# lupa300-card.net
KiCad netlist of a schematic drawn in EAGLE
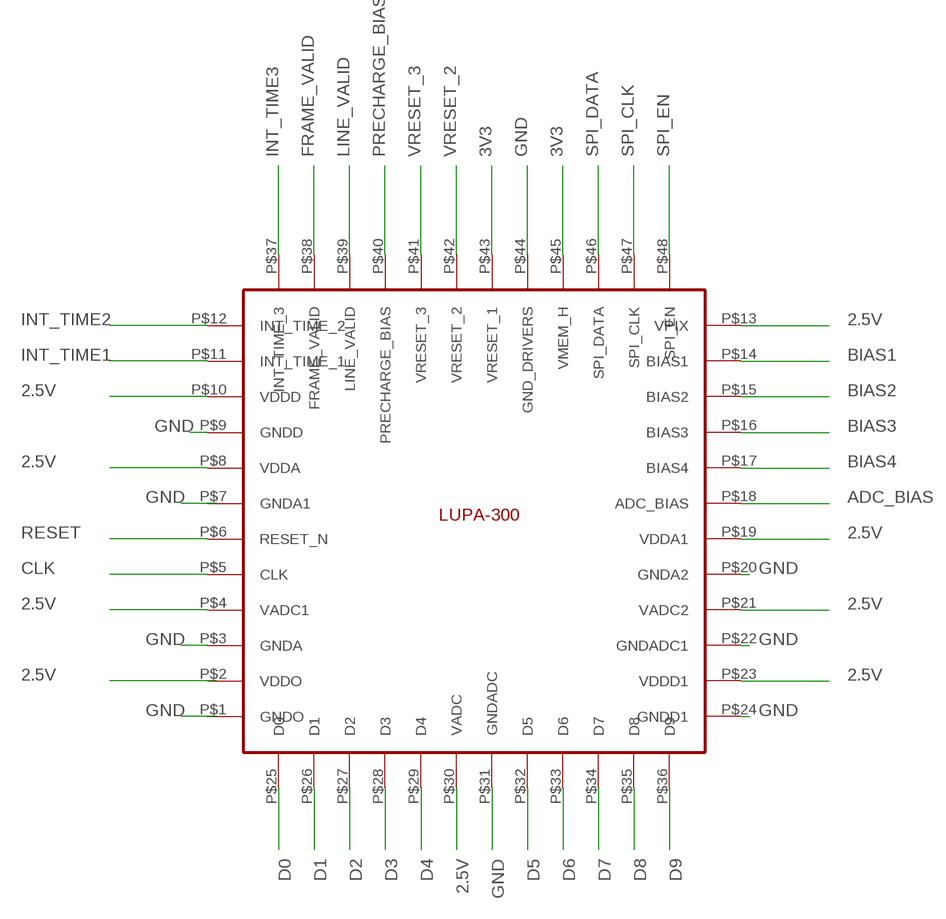
[diagram p0: schematic, sheet 1]
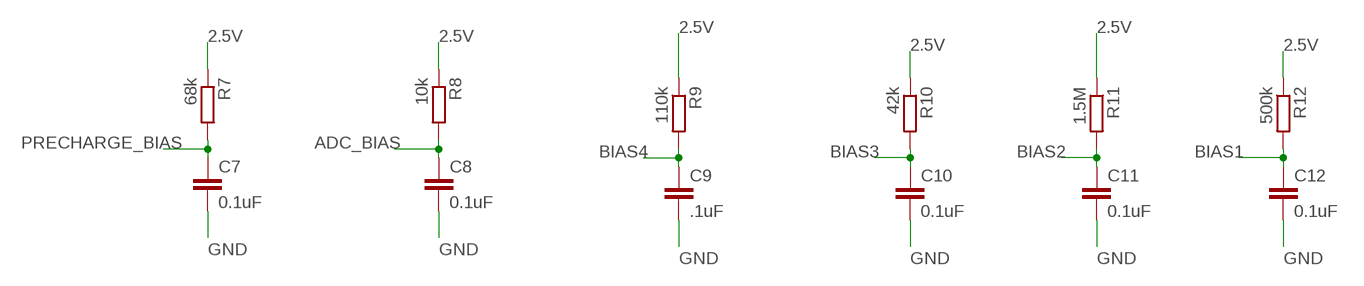
[diagram p1: schematic, sheet 2]
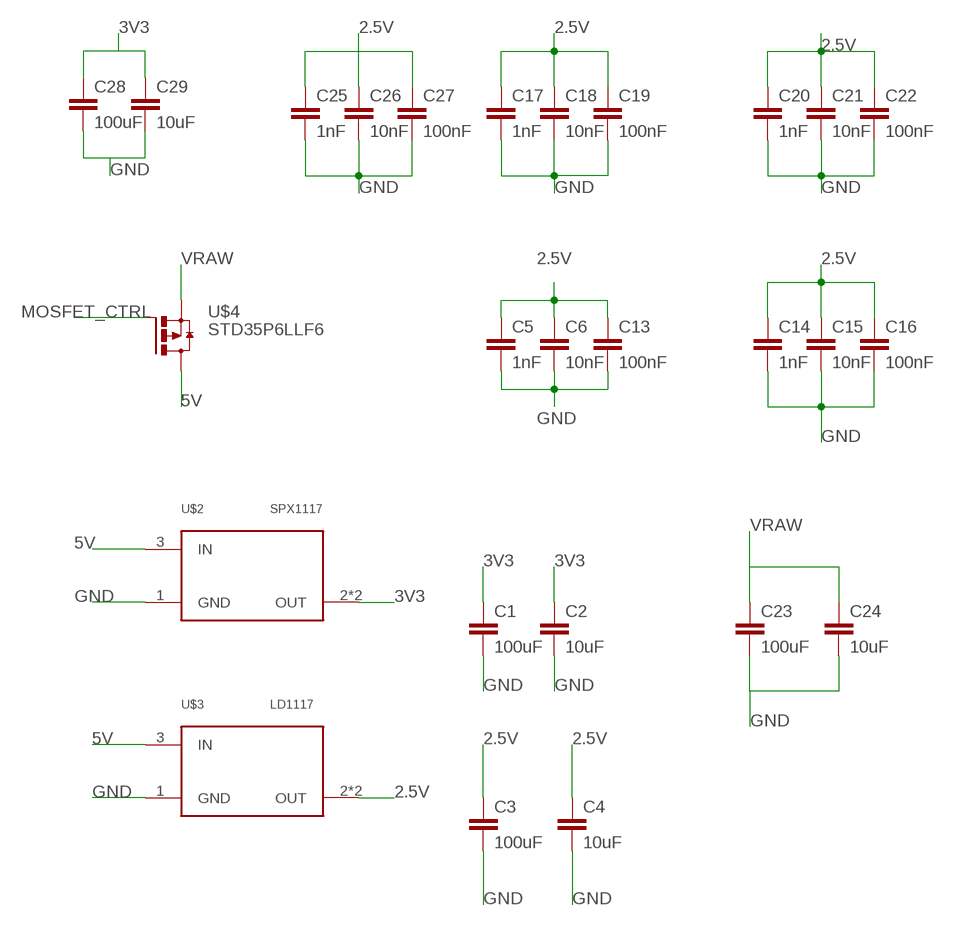
[diagram p2: schematic, sheet 3]
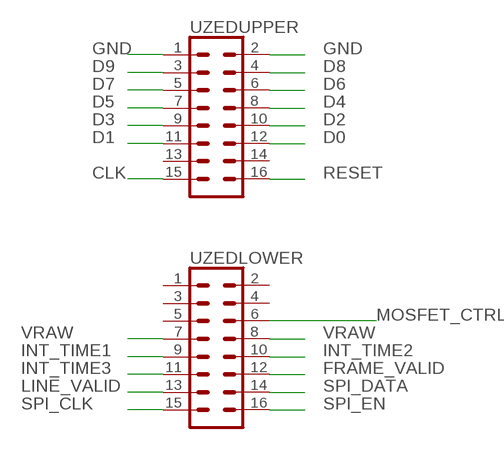
[diagram p3: schematic, sheet 4]

(export (version "E")
  (design (tool "Eeschema 10.0.6"))
  (components
    (comp (ref "C7")
      (value "0.1uF")
      (footprint "eagle-import:C0603K")
      (libsource (lib "eagle-import") (part "C-EUC0603K"))
    )
    (comp (ref "C8")
      (value "0.1uF")
      (footprint "eagle-import:C0603K")
      (libsource (lib "eagle-import") (part "C-EUC0603K"))
    )
    (comp (ref "C9")
      (value ".1uF")
      (footprint "eagle-import:C0603K")
      (libsource (lib "eagle-import") (part "C-EUC0603K"))
    )
    (comp (ref "C10")
      (value "0.1uF")
      (footprint "eagle-import:C0603K")
      (libsource (lib "eagle-import") (part "C-EUC0603K"))
    )
    (comp (ref "C11")
      (value "0.1uF")
      (footprint "eagle-import:C0603K")
      (libsource (lib "eagle-import") (part "C-EUC0603K"))
    )
    (comp (ref "C12")
      (value "0.1uF")
      (footprint "eagle-import:C0603K")
      (libsource (lib "eagle-import") (part "C-EUC0603K"))
    )
    (comp (ref "R7")
      (value "68k")
      (footprint "eagle-import:R0603")
      (libsource (lib "eagle-import") (part "R-EU_R0603"))
    )
    (comp (ref "R8")
      (value "10k")
      (footprint "eagle-import:R0603")
      (libsource (lib "eagle-import") (part "R-EU_R0603"))
    )
    (comp (ref "R9")
      (value "110k")
      (footprint "eagle-import:R0603")
      (libsource (lib "eagle-import") (part "R-EU_R0603"))
    )
    (comp (ref "R10")
      (value "42k")
      (footprint "eagle-import:R0603")
      (libsource (lib "eagle-import") (part "R-EU_R0603"))
    )
    (comp (ref "R11")
      (value "1.5M")
      (footprint "eagle-import:R0603")
      (libsource (lib "eagle-import") (part "R-EU_R0603"))
    )
    (comp (ref "R12")
      (value "500k")
      (footprint "eagle-import:R0603")
      (libsource (lib "eagle-import") (part "R-EU_R0603"))
    )
    (comp (ref "U$1")
      (value "LUPA300")
      (footprint "eagle-import:LUPA300")
      (libsource (lib "eagle-import") (part "LUPA300"))
    )
    (comp (ref "C1")
      (value "100uF")
      (footprint "eagle-import:C1206K")
      (libsource (lib "eagle-import") (part "C-EUC1206K"))
    )
    (comp (ref "C2")
      (value "10uF")
      (footprint "eagle-import:C1206K")
      (libsource (lib "eagle-import") (part "C-EUC1206K"))
    )
    (comp (ref "C3")
      (value "100uF")
      (footprint "eagle-import:C1206K")
      (libsource (lib "eagle-import") (part "C-EUC1206K"))
    )
    (comp (ref "C4")
      (value "10uF")
      (footprint "eagle-import:C1206K")
      (libsource (lib "eagle-import") (part "C-EUC1206K"))
    )
    (comp (ref "C5")
      (value "1nF")
      (footprint "eagle-import:C0603")
      (libsource (lib "eagle-import") (part "C-EUC0603"))
    )
    (comp (ref "C6")
      (value "10nF")
      (footprint "eagle-import:C0603")
      (libsource (lib "eagle-import") (part "C-EUC0603"))
    )
    (comp (ref "C13")
      (value "100nF")
      (footprint "eagle-import:C0603")
      (libsource (lib "eagle-import") (part "C-EUC0603"))
    )
    (comp (ref "C14")
      (value "1nF")
      (footprint "eagle-import:C0603")
      (libsource (lib "eagle-import") (part "C-EUC0603"))
    )
    (comp (ref "C15")
      (value "10nF")
      (footprint "eagle-import:C0603")
      (libsource (lib "eagle-import") (part "C-EUC0603"))
    )
    (comp (ref "C16")
      (value "100nF")
      (footprint "eagle-import:C0603")
      (libsource (lib "eagle-import") (part "C-EUC0603"))
    )
    (comp (ref "C17")
      (value "1nF")
      (footprint "eagle-import:C0603")
      (libsource (lib "eagle-import") (part "C-EUC0603"))
    )
    (comp (ref "C18")
      (value "10nF")
      (footprint "eagle-import:C0603")
      (libsource (lib "eagle-import") (part "C-EUC0603"))
    )
    (comp (ref "C19")
      (value "100nF")
      (footprint "eagle-import:C0603")
      (libsource (lib "eagle-import") (part "C-EUC0603"))
    )
    (comp (ref "C20")
      (value "1nF")
      (footprint "eagle-import:C0603")
      (libsource (lib "eagle-import") (part "C-EUC0603"))
    )
    (comp (ref "C21")
      (value "10nF")
      (footprint "eagle-import:C0603")
      (libsource (lib "eagle-import") (part "C-EUC0603"))
    )
    (comp (ref "C22")
      (value "100nF")
      (footprint "eagle-import:C0603")
      (libsource (lib "eagle-import") (part "C-EUC0603"))
    )
    (comp (ref "C23")
      (value "100uF")
      (footprint "eagle-import:C1206")
      (libsource (lib "eagle-import") (part "C-EUC1206"))
    )
    (comp (ref "C24")
      (value "10uF")
      (footprint "eagle-import:C1206")
      (libsource (lib "eagle-import") (part "C-EUC1206"))
    )
    (comp (ref "C25")
      (value "1nF")
      (footprint "eagle-import:C0603")
      (libsource (lib "eagle-import") (part "C-EUC0603"))
    )
    (comp (ref "C26")
      (value "10nF")
      (footprint "eagle-import:C0603")
      (libsource (lib "eagle-import") (part "C-EUC0603"))
    )
    (comp (ref "C27")
      (value "100nF")
      (footprint "eagle-import:C0603")
      (libsource (lib "eagle-import") (part "C-EUC0603"))
    )
    (comp (ref "C28")
      (value "100uF")
      (footprint "eagle-import:C0603")
      (libsource (lib "eagle-import") (part "C-EUC0603"))
    )
    (comp (ref "C29")
      (value "10uF")
      (footprint "eagle-import:C0603")
      (libsource (lib "eagle-import") (part "C-EUC0603"))
    )
    (comp (ref "U$2")
      (value "SPX1117")
      (footprint "eagle-import:SOT223")
      (libsource (lib "eagle-import") (part "SPX1117"))
    )
    (comp (ref "U$3")
      (value "LD1117")
      (footprint "eagle-import:SOT223")
      (libsource (lib "eagle-import") (part "LD1117"))
    )
    (comp (ref "U$4")
      (value "STD35P6LLF6")
      (footprint "eagle-import:DPACK")
      (libsource (lib "eagle-import") (part "STD35P6LLF6"))
    )
    (comp (ref "UZEDLOWER")
      (value "CONN_08X2")
      (footprint "eagle-import:2X8")
      (libsource (lib "eagle-import") (part "CONN_08X2"))
    )
    (comp (ref "UZEDUPPER")
      (value "CONN_08X2")
      (footprint "eagle-import:2X8")
      (libsource (lib "eagle-import") (part "CONN_08X2"))
    )
  )
  (nets
    (net (code "1") (name "2.5V") (class "Default")
      (node (ref "C13") (pin "1") (pinfunction "1_1") (pintype "passive"))
      (node (ref "C14") (pin "1") (pinfunction "1_1") (pintype "passive"))
      (node (ref "C15") (pin "1") (pinfunction "1_1") (pintype "passive"))
      (node (ref "C16") (pin "1") (pinfunction "1_1") (pintype "passive"))
      (node (ref "C17") (pin "1") (pinfunction "1_1") (pintype "passive"))
      (node (ref "C18") (pin "1") (pinfunction "1_1") (pintype "passive"))
      (node (ref "C19") (pin "1") (pinfunction "1_1") (pintype "passive"))
      (node (ref "C20") (pin "1") (pinfunction "1_1") (pintype "passive"))
      (node (ref "C21") (pin "1") (pinfunction "1_1") (pintype "passive"))
      (node (ref "C22") (pin "1") (pinfunction "1_1") (pintype "passive"))
      (node (ref "C25") (pin "1") (pinfunction "1_1") (pintype "passive"))
      (node (ref "C26") (pin "1") (pinfunction "1_1") (pintype "passive"))
      (node (ref "C27") (pin "1") (pinfunction "1_1") (pintype "passive"))
      (node (ref "C3") (pin "1") (pinfunction "1_1") (pintype "passive"))
      (node (ref "C4") (pin "1") (pinfunction "1_1") (pintype "passive"))
      (node (ref "C5") (pin "1") (pinfunction "1_1") (pintype "passive"))
      (node (ref "C6") (pin "1") (pinfunction "1_1") (pintype "passive"))
      (node (ref "R10") (pin "1") (pinfunction "1_1") (pintype "passive"))
      (node (ref "R11") (pin "1") (pinfunction "1_1") (pintype "passive"))
      (node (ref "R12") (pin "1") (pinfunction "1_1") (pintype "passive"))
      (node (ref "R7") (pin "1") (pinfunction "1_1") (pintype "passive"))
      (node (ref "R8") (pin "1") (pinfunction "1_1") (pintype "passive"))
      (node (ref "R9") (pin "1") (pinfunction "1_1") (pintype "passive"))
      (node (ref "U$1") (pin "P$10") (pinfunction "VDDD_P$10") (pintype "bidirectional"))
      (node (ref "U$1") (pin "P$13") (pinfunction "VPIX_P$13") (pintype "bidirectional"))
      (node (ref "U$1") (pin "P$19") (pinfunction "VDDA1_P$19") (pintype "bidirectional"))
      (node (ref "U$1") (pin "P$2") (pinfunction "VDDO_P$2") (pintype "bidirectional"))
      (node (ref "U$1") (pin "P$21") (pinfunction "VADC2_P$21") (pintype "bidirectional"))
      (node (ref "U$1") (pin "P$23") (pinfunction "VDDD1_P$23") (pintype "bidirectional"))
      (node (ref "U$1") (pin "P$30") (pinfunction "VADC_P$30") (pintype "bidirectional"))
      (node (ref "U$1") (pin "P$4") (pinfunction "VADC1_P$4") (pintype "bidirectional"))
      (node (ref "U$1") (pin "P$8") (pinfunction "VDDA_P$8") (pintype "bidirectional"))
      (node (ref "U$3") (pin "2") (pinfunction "OUT_2") (pintype "bidirectional"))
      (node (ref "U$3") (pin "4") (pinfunction "OUT_4") (pintype "bidirectional"))
    )
    (net (code "2") (name "3V3") (class "Default")
      (node (ref "C1") (pin "1") (pinfunction "1_1") (pintype "passive"))
      (node (ref "C2") (pin "1") (pinfunction "1_1") (pintype "passive"))
      (node (ref "C28") (pin "1") (pinfunction "1_1") (pintype "passive"))
      (node (ref "C29") (pin "1") (pinfunction "1_1") (pintype "passive"))
      (node (ref "U$1") (pin "P$43") (pinfunction "VRESET_1_P$43") (pintype "bidirectional"))
      (node (ref "U$1") (pin "P$45") (pinfunction "VMEM_H_P$45") (pintype "bidirectional"))
      (node (ref "U$2") (pin "2") (pinfunction "OUT_2") (pintype "bidirectional"))
      (node (ref "U$2") (pin "4") (pinfunction "OUT_4") (pintype "bidirectional"))
    )
    (net (code "3") (name "5V") (class "Default")
      (node (ref "U$2") (pin "3") (pinfunction "IN_3") (pintype "bidirectional"))
      (node (ref "U$3") (pin "3") (pinfunction "IN_3") (pintype "bidirectional"))
      (node (ref "U$4") (pin "2") (pinfunction "D_2") (pintype "passive"))
    )
    (net (code "4") (name "ADC_BIAS") (class "Default")
      (node (ref "C8") (pin "1") (pinfunction "1_1") (pintype "passive"))
      (node (ref "R8") (pin "2") (pinfunction "2_2") (pintype "passive"))
      (node (ref "U$1") (pin "P$18") (pinfunction "ADC_BIAS_P$18") (pintype "bidirectional"))
    )
    (net (code "5") (name "BIAS1") (class "Default")
      (node (ref "C12") (pin "1") (pinfunction "1_1") (pintype "passive"))
      (node (ref "R12") (pin "2") (pinfunction "2_2") (pintype "passive"))
      (node (ref "U$1") (pin "P$14") (pinfunction "BIAS1_P$14") (pintype "bidirectional"))
    )
    (net (code "6") (name "BIAS2") (class "Default")
      (node (ref "C11") (pin "1") (pinfunction "1_1") (pintype "passive"))
      (node (ref "R11") (pin "2") (pinfunction "2_2") (pintype "passive"))
      (node (ref "U$1") (pin "P$15") (pinfunction "BIAS2_P$15") (pintype "bidirectional"))
    )
    (net (code "7") (name "BIAS3") (class "Default")
      (node (ref "C10") (pin "1") (pinfunction "1_1") (pintype "passive"))
      (node (ref "R10") (pin "2") (pinfunction "2_2") (pintype "passive"))
      (node (ref "U$1") (pin "P$16") (pinfunction "BIAS3_P$16") (pintype "bidirectional"))
    )
    (net (code "8") (name "BIAS4") (class "Default")
      (node (ref "C9") (pin "1") (pinfunction "1_1") (pintype "passive"))
      (node (ref "R9") (pin "2") (pinfunction "2_2") (pintype "passive"))
      (node (ref "U$1") (pin "P$17") (pinfunction "BIAS4_P$17") (pintype "bidirectional"))
    )
    (net (code "9") (name "CLK") (class "Default")
      (node (ref "U$1") (pin "P$5") (pinfunction "CLK_P$5") (pintype "bidirectional"))
      (node (ref "UZEDUPPER") (pin "15") (pinfunction "15_15") (pintype "passive"))
    )
    (net (code "10") (name "D0") (class "Default")
      (node (ref "U$1") (pin "P$25") (pinfunction "D0_P$25") (pintype "bidirectional"))
      (node (ref "UZEDUPPER") (pin "12") (pinfunction "12_12") (pintype "passive"))
    )
    (net (code "11") (name "D1") (class "Default")
      (node (ref "U$1") (pin "P$26") (pinfunction "D1_P$26") (pintype "bidirectional"))
      (node (ref "UZEDUPPER") (pin "11") (pinfunction "11_11") (pintype "passive"))
    )
    (net (code "12") (name "D2") (class "Default")
      (node (ref "U$1") (pin "P$27") (pinfunction "D2_P$27") (pintype "bidirectional"))
      (node (ref "UZEDUPPER") (pin "10") (pinfunction "10_10") (pintype "passive"))
    )
    (net (code "13") (name "D3") (class "Default")
      (node (ref "U$1") (pin "P$28") (pinfunction "D3_P$28") (pintype "bidirectional"))
      (node (ref "UZEDUPPER") (pin "9") (pinfunction "9_9") (pintype "passive"))
    )
    (net (code "14") (name "D4") (class "Default")
      (node (ref "U$1") (pin "P$29") (pinfunction "D4_P$29") (pintype "bidirectional"))
      (node (ref "UZEDUPPER") (pin "8") (pinfunction "8_8") (pintype "passive"))
    )
    (net (code "15") (name "D5") (class "Default")
      (node (ref "U$1") (pin "P$32") (pinfunction "D5_P$32") (pintype "bidirectional"))
      (node (ref "UZEDUPPER") (pin "7") (pinfunction "7_7") (pintype "passive"))
    )
    (net (code "16") (name "D6") (class "Default")
      (node (ref "U$1") (pin "P$33") (pinfunction "D6_P$33") (pintype "bidirectional"))
      (node (ref "UZEDUPPER") (pin "6") (pinfunction "6_6") (pintype "passive"))
    )
    (net (code "17") (name "D7") (class "Default")
      (node (ref "U$1") (pin "P$34") (pinfunction "D7_P$34") (pintype "bidirectional"))
      (node (ref "UZEDUPPER") (pin "5") (pinfunction "5_5") (pintype "passive"))
    )
    (net (code "18") (name "D8") (class "Default")
      (node (ref "U$1") (pin "P$35") (pinfunction "D8_P$35") (pintype "bidirectional"))
      (node (ref "UZEDUPPER") (pin "4") (pinfunction "4_4") (pintype "passive"))
    )
    (net (code "19") (name "D9") (class "Default")
      (node (ref "U$1") (pin "P$36") (pinfunction "D9_P$36") (pintype "bidirectional"))
      (node (ref "UZEDUPPER") (pin "3") (pinfunction "3_3") (pintype "passive"))
    )
    (net (code "20") (name "FRAME_VALID") (class "Default")
      (node (ref "U$1") (pin "P$38") (pinfunction "FRAME_VALID_P$38") (pintype "bidirectional"))
      (node (ref "UZEDLOWER") (pin "12") (pinfunction "12_12") (pintype "passive"))
    )
    (net (code "21") (name "GND") (class "Default")
      (node (ref "C1") (pin "2") (pinfunction "2_2") (pintype "passive"))
      (node (ref "C10") (pin "2") (pinfunction "2_2") (pintype "passive"))
      (node (ref "C11") (pin "2") (pinfunction "2_2") (pintype "passive"))
      (node (ref "C12") (pin "2") (pinfunction "2_2") (pintype "passive"))
      (node (ref "C13") (pin "2") (pinfunction "2_2") (pintype "passive"))
      (node (ref "C14") (pin "2") (pinfunction "2_2") (pintype "passive"))
      (node (ref "C15") (pin "2") (pinfunction "2_2") (pintype "passive"))
      (node (ref "C16") (pin "2") (pinfunction "2_2") (pintype "passive"))
      (node (ref "C17") (pin "2") (pinfunction "2_2") (pintype "passive"))
      (node (ref "C18") (pin "2") (pinfunction "2_2") (pintype "passive"))
      (node (ref "C19") (pin "2") (pinfunction "2_2") (pintype "passive"))
      (node (ref "C2") (pin "2") (pinfunction "2_2") (pintype "passive"))
      (node (ref "C20") (pin "2") (pinfunction "2_2") (pintype "passive"))
      (node (ref "C21") (pin "2") (pinfunction "2_2") (pintype "passive"))
      (node (ref "C22") (pin "2") (pinfunction "2_2") (pintype "passive"))
      (node (ref "C23") (pin "2") (pinfunction "2_2") (pintype "passive"))
      (node (ref "C24") (pin "2") (pinfunction "2_2") (pintype "passive"))
      (node (ref "C25") (pin "2") (pinfunction "2_2") (pintype "passive"))
      (node (ref "C26") (pin "2") (pinfunction "2_2") (pintype "passive"))
      (node (ref "C27") (pin "2") (pinfunction "2_2") (pintype "passive"))
      (node (ref "C28") (pin "2") (pinfunction "2_2") (pintype "passive"))
      (node (ref "C29") (pin "2") (pinfunction "2_2") (pintype "passive"))
      (node (ref "C3") (pin "2") (pinfunction "2_2") (pintype "passive"))
      (node (ref "C4") (pin "2") (pinfunction "2_2") (pintype "passive"))
      (node (ref "C5") (pin "2") (pinfunction "2_2") (pintype "passive"))
      (node (ref "C6") (pin "2") (pinfunction "2_2") (pintype "passive"))
      (node (ref "C7") (pin "2") (pinfunction "2_2") (pintype "passive"))
      (node (ref "C8") (pin "2") (pinfunction "2_2") (pintype "passive"))
      (node (ref "C9") (pin "2") (pinfunction "2_2") (pintype "passive"))
      (node (ref "U$1") (pin "P$1") (pinfunction "GNDO_P$1") (pintype "bidirectional"))
      (node (ref "U$1") (pin "P$20") (pinfunction "GNDA2_P$20") (pintype "bidirectional"))
      (node (ref "U$1") (pin "P$22") (pinfunction "GNDADC1_P$22") (pintype "bidirectional"))
      (node (ref "U$1") (pin "P$24") (pinfunction "GNDD1_P$24") (pintype "bidirectional"))
      (node (ref "U$1") (pin "P$3") (pinfunction "GNDA_P$3") (pintype "bidirectional"))
      (node (ref "U$1") (pin "P$31") (pinfunction "GNDADC_P$31") (pintype "bidirectional"))
      (node (ref "U$1") (pin "P$44") (pinfunction "GND_DRIVERS_P$44") (pintype "bidirectional"))
      (node (ref "U$1") (pin "P$9") (pinfunction "GNDD_P$9") (pintype "bidirectional"))
      (node (ref "U$2") (pin "1") (pinfunction "GND_1") (pintype "bidirectional"))
      (node (ref "U$3") (pin "1") (pinfunction "GND_1") (pintype "bidirectional"))
      (node (ref "UZEDUPPER") (pin "1") (pinfunction "1_1") (pintype "passive"))
      (node (ref "UZEDUPPER") (pin "2") (pinfunction "2_2") (pintype "passive"))
    )
    (net (code "22") (name "INT_TIME1") (class "Default")
      (node (ref "U$1") (pin "P$11") (pinfunction "INT_TIME_1_P$11") (pintype "bidirectional"))
      (node (ref "UZEDLOWER") (pin "9") (pinfunction "9_9") (pintype "passive"))
    )
    (net (code "23") (name "INT_TIME2") (class "Default")
      (node (ref "U$1") (pin "P$12") (pinfunction "INT_TIME_2_P$12") (pintype "bidirectional"))
      (node (ref "UZEDLOWER") (pin "10") (pinfunction "10_10") (pintype "passive"))
    )
    (net (code "24") (name "INT_TIME3") (class "Default")
      (node (ref "U$1") (pin "P$37") (pinfunction "INT_TIME_3_P$37") (pintype "bidirectional"))
      (node (ref "UZEDLOWER") (pin "11") (pinfunction "11_11") (pintype "passive"))
    )
    (net (code "25") (name "LINE_VALID") (class "Default")
      (node (ref "U$1") (pin "P$39") (pinfunction "LINE_VALID_P$39") (pintype "bidirectional"))
      (node (ref "UZEDLOWER") (pin "13") (pinfunction "13_13") (pintype "passive"))
    )
    (net (code "26") (name "MOSFET_CTRL") (class "Default")
      (node (ref "U$4") (pin "1") (pinfunction "G_1") (pintype "passive"))
      (node (ref "UZEDLOWER") (pin "6") (pinfunction "6_6") (pintype "passive"))
    )
    (net (code "27") (name "PRECHARGE_BIAS") (class "Default")
      (node (ref "C7") (pin "1") (pinfunction "1_1") (pintype "passive"))
      (node (ref "R7") (pin "2") (pinfunction "2_2") (pintype "passive"))
      (node (ref "U$1") (pin "P$40") (pinfunction "PRECHARGE_BIAS_P$40") (pintype "bidirectional"))
    )
    (net (code "28") (name "RESET") (class "Default")
      (node (ref "U$1") (pin "P$6") (pinfunction "RESET_N_P$6") (pintype "bidirectional"))
      (node (ref "UZEDUPPER") (pin "16") (pinfunction "16_16") (pintype "passive"))
    )
    (net (code "29") (name "SPI_CLK") (class "Default")
      (node (ref "U$1") (pin "P$47") (pinfunction "SPI_CLK_P$47") (pintype "bidirectional"))
      (node (ref "UZEDLOWER") (pin "15") (pinfunction "15_15") (pintype "passive"))
    )
    (net (code "30") (name "SPI_DATA") (class "Default")
      (node (ref "U$1") (pin "P$46") (pinfunction "SPI_DATA_P$46") (pintype "bidirectional"))
      (node (ref "UZEDLOWER") (pin "14") (pinfunction "14_14") (pintype "passive"))
    )
    (net (code "31") (name "SPI_EN") (class "Default")
      (node (ref "U$1") (pin "P$48") (pinfunction "SPI_EN_P$48") (pintype "bidirectional"))
      (node (ref "UZEDLOWER") (pin "16") (pinfunction "16_16") (pintype "passive"))
    )
    (net (code "32") (name "VRAW") (class "Default")
      (node (ref "C23") (pin "1") (pinfunction "1_1") (pintype "passive"))
      (node (ref "C24") (pin "1") (pinfunction "1_1") (pintype "passive"))
      (node (ref "U$4") (pin "3") (pinfunction "S_3") (pintype "passive"))
      (node (ref "UZEDLOWER") (pin "7") (pinfunction "7_7") (pintype "passive"))
      (node (ref "UZEDLOWER") (pin "8") (pinfunction "8_8") (pintype "passive"))
    )
    (net (code "33") (name "VRESET_2") (class "Default")
      (node (ref "U$1") (pin "P$42") (pinfunction "VRESET_2_P$42") (pintype "bidirectional"))
    )
    (net (code "34") (name "VRESET_3") (class "Default")
      (node (ref "U$1") (pin "P$41") (pinfunction "VRESET_3_P$41") (pintype "bidirectional"))
    )
    (net (code "35") (name "unconnected-(U$1-GNDA1-PadP$7)") (class "Default")
      (node (ref "U$1") (pin "P$7") (pinfunction "GNDA1_P$7") (pintype "bidirectional"))
    )
    (net (code "36") (name "unconnected-(UZEDLOWER-Pad1)") (class "Default")
      (node (ref "UZEDLOWER") (pin "1") (pinfunction "1_1") (pintype "passive"))
    )
    (net (code "37") (name "unconnected-(UZEDLOWER-Pad2)") (class "Default")
      (node (ref "UZEDLOWER") (pin "2") (pinfunction "2_2") (pintype "passive"))
    )
    (net (code "38") (name "unconnected-(UZEDLOWER-Pad3)") (class "Default")
      (node (ref "UZEDLOWER") (pin "3") (pinfunction "3_3") (pintype "passive"))
    )
    (net (code "39") (name "unconnected-(UZEDLOWER-Pad4)") (class "Default")
      (node (ref "UZEDLOWER") (pin "4") (pinfunction "4_4") (pintype "passive"))
    )
    (net (code "40") (name "unconnected-(UZEDLOWER-Pad5)") (class "Default")
      (node (ref "UZEDLOWER") (pin "5") (pinfunction "5_5") (pintype "passive"))
    )
    (net (code "41") (name "unconnected-(UZEDUPPER-Pad13)") (class "Default")
      (node (ref "UZEDUPPER") (pin "13") (pinfunction "13_13") (pintype "passive"))
    )
    (net (code "42") (name "unconnected-(UZEDUPPER-Pad14)") (class "Default")
      (node (ref "UZEDUPPER") (pin "14") (pinfunction "14_14") (pintype "passive"))
    )
  )
)
